# CPU.net
KiCad netlist of a schematic drawn in Altium Designer
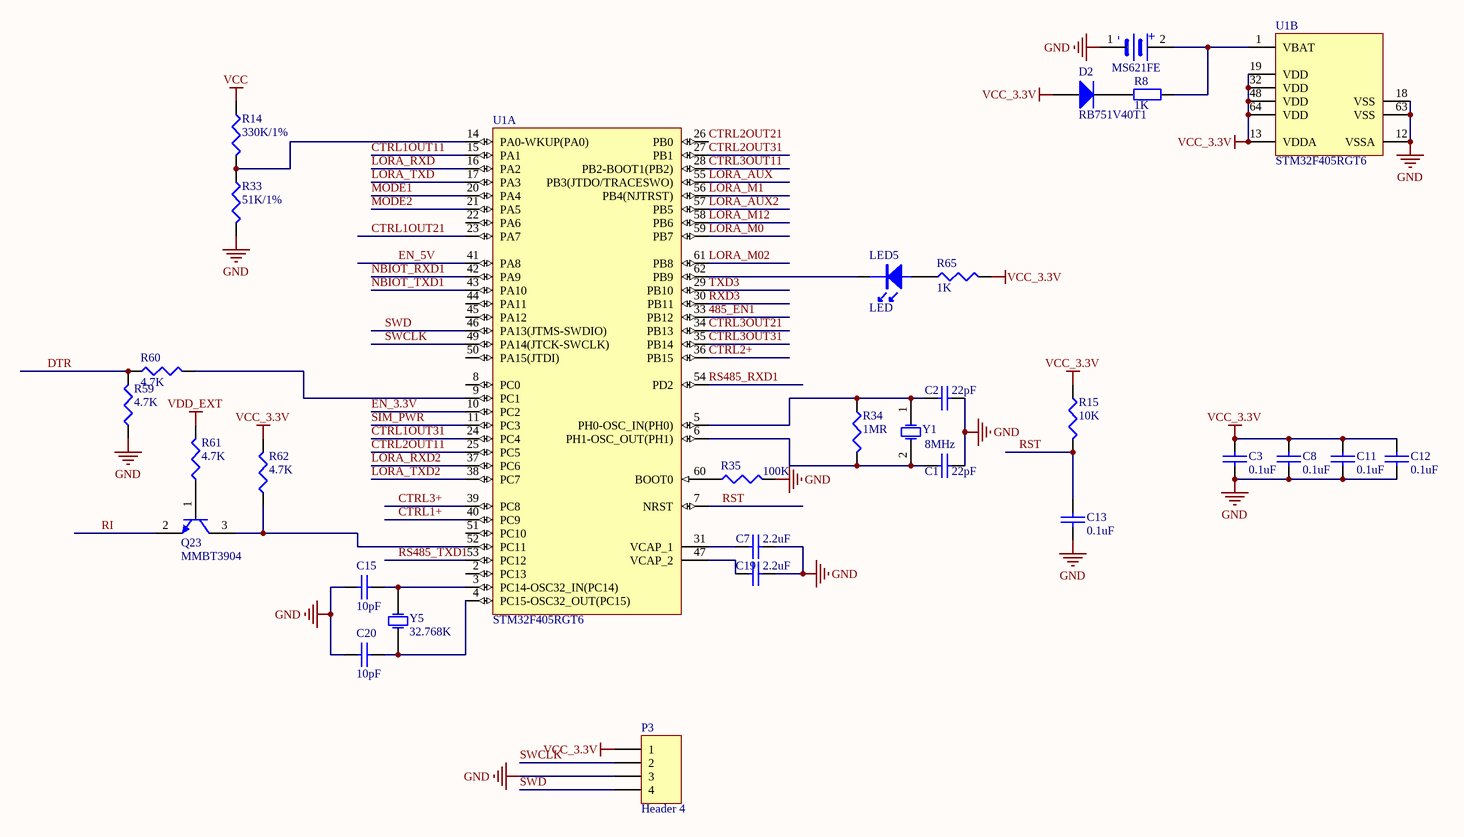
[diagram p0: CPU.SchDoc]

(export (version "E")
  (design (tool "Eeschema 10.0.6"))
  (components
    (comp (ref "C1")
      (value "22pF")
      (footprint "0603c")
      (description "Capacitor")
      (libsource (lib "SM") (part "CAP"))
    )
    (comp (ref "C2")
      (value "22pF")
      (footprint "0603c")
      (description "Capacitor")
      (libsource (lib "SM") (part "CAP"))
    )
    (comp (ref "C3")
      (value "0.1uF")
      (footprint "0603c")
      (description "Capacitor")
      (libsource (lib "SM") (part "CAP"))
    )
    (comp (ref "C7")
      (value "2.2uF")
      (footprint "0603c")
      (description "Capacitor")
      (libsource (lib "SM") (part "CAP"))
    )
    (comp (ref "C8")
      (value "0.1uF")
      (footprint "0603c")
      (description "Capacitor")
      (libsource (lib "SM") (part "CAP"))
    )
    (comp (ref "C11")
      (value "0.1uF")
      (footprint "0603c")
      (description "Capacitor")
      (libsource (lib "SM") (part "CAP"))
    )
    (comp (ref "C12")
      (value "0.1uF")
      (footprint "0603c")
      (description "Capacitor")
      (libsource (lib "SM") (part "CAP"))
    )
    (comp (ref "C13")
      (value "0.1uF")
      (footprint "0603c")
      (description "Capacitor")
      (libsource (lib "SM") (part "CAP"))
    )
    (comp (ref "C15")
      (value "10pF")
      (footprint "0603c")
      (description "Capacitor")
      (libsource (lib "SM") (part "CAP"))
    )
    (comp (ref "C19")
      (value "2.2uF")
      (footprint "0603c")
      (description "Capacitor")
      (libsource (lib "SM") (part "CAP"))
    )
    (comp (ref "C20")
      (value "10pF")
      (footprint "0603c")
      (description "Capacitor")
      (libsource (lib "SM") (part "CAP"))
    )
    (comp (ref "D2")
      (value "RB751V40T1")
      (footprint "SOD323")
      (description "Default Diode")
      (fields (field (name "PUBLISHER") "Altium Limited"))
      (libsource (lib "Miscellaneous Devices") (part "Diode"))
    )
    (comp (ref "LED5") (value "LED") (footprint "0603LED") (libsource (lib "我的元件库") (part "LED")))
    (comp (ref "MS621FE")
      (value "SBatery")
      (footprint "MS621FE")
      (libsource (lib "Myself_1") (part "SBatery"))
    )
    (comp (ref "P3")
      (value "Header 4")
      (footprint "HDR1X4")
      (description "Header, 4-Pin")
      (fields (field (name "PUBLISHER") "Altium Limited"))
      (libsource (lib "Miscellaneous Connectors") (part "Header 4"))
    )
    (comp (ref "Q23") (value "MMBT3904") (footprint "SOT23-3") (libsource (lib "Schlib1") (part "NPN")))
    (comp (ref "R8")
      (value "1K")
      (footprint "0603R")
      (description "Resistor")
      (fields (field (name "PUBLISHER") "Altium Limited"))
      (libsource (lib "Miscellaneous Devices") (part "Res2"))
    )
    (comp (ref "R14")
      (value "330K/1%")
      (footprint "0603R")
      (description "Resistor")
      (fields (field (name "PUBLISHER") "Altium Limited"))
      (libsource (lib "SM") (part "Res3"))
    )
    (comp (ref "R15")
      (value "10K")
      (footprint "0603R")
      (description "Resistor")
      (fields (field (name "PUBLISHER") "Altium Limited"))
      (libsource (lib "SM") (part "Res3"))
    )
    (comp (ref "R33")
      (value "51K/1%")
      (footprint "0603R")
      (description "Resistor")
      (fields (field (name "PUBLISHER") "Altium Limited"))
      (libsource (lib "SM") (part "Res3"))
    )
    (comp (ref "R34")
      (value "1MR")
      (footprint "0603R")
      (description "Resistor")
      (fields (field (name "PUBLISHER") "Altium Limited"))
      (libsource (lib "SM") (part "Res3"))
    )
    (comp (ref "R35")
      (value "100K")
      (footprint "0603R")
      (description "Resistor")
      (fields (field (name "PUBLISHER") "Altium Limited"))
      (libsource (lib "SM") (part "Res3"))
    )
    (comp (ref "R59")
      (value "4.7K")
      (footprint "0603R")
      (libsource (lib "ZWLIntegrated_Library") (part "RES1"))
    )
    (comp (ref "R60")
      (value "4.7K")
      (footprint "0603R")
      (libsource (lib "ZWLIntegrated_Library") (part "RES1"))
    )
    (comp (ref "R61")
      (value "4.7K")
      (footprint "0603R")
      (libsource (lib "ZWLIntegrated_Library") (part "RES1"))
    )
    (comp (ref "R62")
      (value "4.7K")
      (footprint "0603R")
      (libsource (lib "ZWLIntegrated_Library") (part "RES1"))
    )
    (comp (ref "R65")
      (value "1K")
      (footprint "0603R")
      (libsource (lib "ZWLIntegrated_Library") (part "RES1"))
    )
    (comp (ref "U1")
      (value "STM32F405RGT6")
      (footprint "LQFP-64")
      (fields (field (name "MANUFACTURER") "STMicroelectronics"))
      (libsource (lib "STMicroelectronics STM32 F4") (part "STM32F405RGT6"))
    )
    (comp (ref "Y1")
      (value "8MHz")
      (footprint "CRAY_5032")
      (description "Crystal Oscillator")
      (fields (field (name "PUBLISHER") "Altium Limited"))
      (libsource (lib "Miscellaneous Devices") (part "XTAL"))
    )
    (comp (ref "Y5")
      (value "32.768K")
      (footprint "32.768K")
      (description "Crystal Oscillator")
      (fields (field (name "PUBLISHER") "Altium Limited"))
      (libsource (lib "") (part "XTAL_1"))
    )
  )
  (nets
    (net (code "1") (name "/485_EN1") (class "Default")
      (node (ref "U1") (pin "33") (pinfunction "PB12_33") (pintype "bidirectional"))
    )
    (net (code "2") (name "/CTRL1+") (class "Default")
      (node (ref "U1") (pin "40") (pinfunction "PC9_40") (pintype "bidirectional"))
    )
    (net (code "3") (name "/CTRL1OUT11") (class "Default")
      (node (ref "U1") (pin "15") (pinfunction "PA1_15") (pintype "bidirectional"))
    )
    (net (code "4") (name "/CTRL1OUT21") (class "Default")
      (node (ref "U1") (pin "23") (pinfunction "PA7_23") (pintype "bidirectional"))
    )
    (net (code "5") (name "/CTRL1OUT31") (class "Default")
      (node (ref "U1") (pin "24") (pinfunction "PC4_24") (pintype "bidirectional"))
    )
    (net (code "6") (name "/CTRL2+") (class "Default")
      (node (ref "U1") (pin "36") (pinfunction "PB15_36") (pintype "bidirectional"))
    )
    (net (code "7") (name "/CTRL2OUT11") (class "Default")
      (node (ref "U1") (pin "25") (pinfunction "PC5_25") (pintype "bidirectional"))
    )
    (net (code "8") (name "/CTRL2OUT21") (class "Default")
      (node (ref "U1") (pin "26") (pinfunction "PB0_26") (pintype "bidirectional"))
    )
    (net (code "9") (name "/CTRL2OUT31") (class "Default")
      (node (ref "U1") (pin "27") (pinfunction "PB1_27") (pintype "bidirectional"))
    )
    (net (code "10") (name "/CTRL3+") (class "Default")
      (node (ref "U1") (pin "39") (pinfunction "PC8_39") (pintype "bidirectional"))
    )
    (net (code "11") (name "/CTRL3OUT11") (class "Default")
      (node (ref "U1") (pin "28") (pinfunction "PB2-BOOT1(PB2)_28") (pintype "bidirectional"))
    )
    (net (code "12") (name "/CTRL3OUT21") (class "Default")
      (node (ref "U1") (pin "34") (pinfunction "PB13_34") (pintype "bidirectional"))
    )
    (net (code "13") (name "/CTRL3OUT31") (class "Default")
      (node (ref "U1") (pin "35") (pinfunction "PB14_35") (pintype "bidirectional"))
    )
    (net (code "14") (name "/DTR") (class "Default")
      (node (ref "R59") (pin "2") (pinfunction "2_2") (pintype "passive"))
      (node (ref "R60") (pin "1") (pinfunction "1_1") (pintype "passive"))
    )
    (net (code "15") (name "/EN_3.3V") (class "Default")
      (node (ref "U1") (pin "10") (pinfunction "PC2_10") (pintype "bidirectional"))
    )
    (net (code "16") (name "/EN_5V") (class "Default")
      (node (ref "U1") (pin "41") (pinfunction "PA8_41") (pintype "bidirectional"))
    )
    (net (code "17") (name "/LORA_AUX") (class "Default")
      (node (ref "U1") (pin "55") (pinfunction "PB3(JTDO/TRACESWO)_55") (pintype "bidirectional"))
    )
    (net (code "18") (name "/LORA_AUX2") (class "Default")
      (node (ref "U1") (pin "57") (pinfunction "PB5_57") (pintype "bidirectional"))
    )
    (net (code "19") (name "/LORA_M0") (class "Default")
      (node (ref "U1") (pin "59") (pinfunction "PB7_59") (pintype "bidirectional"))
    )
    (net (code "20") (name "/LORA_M1") (class "Default")
      (node (ref "U1") (pin "56") (pinfunction "PB4(NJTRST)_56") (pintype "bidirectional"))
    )
    (net (code "21") (name "/LORA_M02") (class "Default")
      (node (ref "U1") (pin "61") (pinfunction "PB8_61") (pintype "bidirectional"))
    )
    (net (code "22") (name "/LORA_M12") (class "Default")
      (node (ref "U1") (pin "58") (pinfunction "PB6_58") (pintype "bidirectional"))
    )
    (net (code "23") (name "/LORA_RXD") (class "Default")
      (node (ref "U1") (pin "16") (pinfunction "PA2_16") (pintype "bidirectional"))
    )
    (net (code "24") (name "/LORA_RXD2") (class "Default")
      (node (ref "U1") (pin "37") (pinfunction "PC6_37") (pintype "bidirectional"))
    )
    (net (code "25") (name "/LORA_TXD") (class "Default")
      (node (ref "U1") (pin "17") (pinfunction "PA3_17") (pintype "bidirectional"))
    )
    (net (code "26") (name "/LORA_TXD2") (class "Default")
      (node (ref "U1") (pin "38") (pinfunction "PC7_38") (pintype "bidirectional"))
    )
    (net (code "27") (name "/MODE1") (class "Default")
      (node (ref "U1") (pin "20") (pinfunction "PA4_20") (pintype "bidirectional"))
    )
    (net (code "28") (name "/MODE2") (class "Default")
      (node (ref "U1") (pin "21") (pinfunction "PA5_21") (pintype "bidirectional"))
    )
    (net (code "29") (name "/NBIOT_RXD1") (class "Default")
      (node (ref "U1") (pin "42") (pinfunction "PA9_42") (pintype "bidirectional"))
    )
    (net (code "30") (name "/NBIOT_TXD1") (class "Default")
      (node (ref "U1") (pin "43") (pinfunction "PA10_43") (pintype "bidirectional"))
    )
    (net (code "31") (name "/RI") (class "Default")
      (node (ref "Q23") (pin "2") (pinfunction "E_2") (pintype "passive"))
    )
    (net (code "32") (name "/RS485_RXD1") (class "Default")
      (node (ref "U1") (pin "54") (pinfunction "PD2_54") (pintype "bidirectional"))
    )
    (net (code "33") (name "/RS485_TXD1") (class "Default")
      (node (ref "U1") (pin "53") (pinfunction "PC12_53") (pintype "bidirectional"))
    )
    (net (code "34") (name "/RST") (class "Default")
      (node (ref "C13") (pin "2") (pinfunction "2_2") (pintype "passive"))
      (node (ref "R15") (pin "2") (pinfunction "2_2") (pintype "passive"))
      (node (ref "U1") (pin "7") (pinfunction "NRST_7") (pintype "bidirectional"))
    )
    (net (code "35") (name "/RXD3") (class "Default")
      (node (ref "U1") (pin "30") (pinfunction "PB11_30") (pintype "bidirectional"))
    )
    (net (code "36") (name "/SIM_PWR") (class "Default")
      (node (ref "U1") (pin "11") (pinfunction "PC3_11") (pintype "bidirectional"))
    )
    (net (code "37") (name "/SWCLK") (class "Default")
      (node (ref "P3") (pin "2") (pinfunction "2_2") (pintype "passive"))
      (node (ref "U1") (pin "49") (pinfunction "PA14(JTCK-SWCLK)_49") (pintype "bidirectional"))
    )
    (net (code "38") (name "/SWD") (class "Default")
      (node (ref "P3") (pin "4") (pinfunction "4_4") (pintype "passive"))
      (node (ref "U1") (pin "46") (pinfunction "PA13(JTMS-SWDIO)_46") (pintype "bidirectional"))
    )
    (net (code "39") (name "/TXD3") (class "Default")
      (node (ref "U1") (pin "29") (pinfunction "PB10_29") (pintype "bidirectional"))
    )
    (net (code "40") (name "GND") (class "Default")
      (node (ref "C1") (pin "1") (pinfunction "1_1") (pintype "passive"))
      (node (ref "C11") (pin "1") (pinfunction "1_1") (pintype "passive"))
      (node (ref "C12") (pin "1") (pinfunction "1_1") (pintype "passive"))
      (node (ref "C13") (pin "1") (pinfunction "1_1") (pintype "passive"))
      (node (ref "C15") (pin "1") (pinfunction "1_1") (pintype "passive"))
      (node (ref "C19") (pin "1") (pinfunction "1_1") (pintype "passive"))
      (node (ref "C2") (pin "1") (pinfunction "1_1") (pintype "passive"))
      (node (ref "C20") (pin "1") (pinfunction "1_1") (pintype "passive"))
      (node (ref "C3") (pin "1") (pinfunction "1_1") (pintype "passive"))
      (node (ref "C7") (pin "1") (pinfunction "1_1") (pintype "passive"))
      (node (ref "C8") (pin "1") (pinfunction "1_1") (pintype "passive"))
      (node (ref "MS621FE") (pin "1") (pinfunction "1_1") (pintype "passive"))
      (node (ref "P3") (pin "3") (pinfunction "3_3") (pintype "passive"))
      (node (ref "R33") (pin "2") (pinfunction "2_2") (pintype "passive"))
      (node (ref "R35") (pin "2") (pinfunction "2_2") (pintype "passive"))
      (node (ref "R59") (pin "1") (pinfunction "1_1") (pintype "passive"))
      (node (ref "U1") (pin "12") (pinfunction "VSSA_12") (pintype "power_in"))
      (node (ref "U1") (pin "18") (pinfunction "VSS_18") (pintype "power_in"))
      (node (ref "U1") (pin "63") (pinfunction "VSS_63") (pintype "power_in"))
    )
    (net (code "41") (name "Net-(D2-K)") (class "Default")
      (node (ref "D2") (pin "2") (pinfunction "K_2") (pintype "passive"))
      (node (ref "R8") (pin "1") (pinfunction "1_1") (pintype "passive"))
    )
    (net (code "42") (name "Net-(LED5-Pad1)") (class "Default")
      (node (ref "LED5") (pin "1") (pinfunction "1_1") (pintype "passive"))
      (node (ref "R65") (pin "1") (pinfunction "1_1") (pintype "passive"))
    )
    (net (code "43") (name "Net-(Q23-B)") (class "Default")
      (node (ref "Q23") (pin "1") (pinfunction "B_1") (pintype "passive"))
      (node (ref "R61") (pin "1") (pinfunction "1_1") (pintype "passive"))
    )
    (net (code "44") (name "Net-(Q23-C)") (class "Default")
      (node (ref "Q23") (pin "3") (pinfunction "C_3") (pintype "passive"))
      (node (ref "R62") (pin "1") (pinfunction "1_1") (pintype "passive"))
      (node (ref "U1") (pin "52") (pinfunction "PC11_52") (pintype "bidirectional"))
    )
    (net (code "45") (name "Net-(U1A-BOOT0)") (class "Default")
      (node (ref "R35") (pin "1") (pinfunction "1_1") (pintype "passive"))
      (node (ref "U1") (pin "60") (pinfunction "BOOT0_60") (pintype "input"))
    )
    (net (code "46") (name "Net-(U1A-PA0-WKUP(PA0))") (class "Default")
      (node (ref "R14") (pin "2") (pinfunction "2_2") (pintype "passive"))
      (node (ref "R33") (pin "1") (pinfunction "1_1") (pintype "passive"))
      (node (ref "U1") (pin "14") (pinfunction "PA0-WKUP(PA0)_14") (pintype "bidirectional"))
    )
    (net (code "47") (name "Net-(U1A-PB9)") (class "Default")
      (node (ref "LED5") (pin "2") (pinfunction "2_2") (pintype "passive"))
      (node (ref "U1") (pin "62") (pinfunction "PB9_62") (pintype "bidirectional"))
    )
    (net (code "48") (name "Net-(U1A-PC1)") (class "Default")
      (node (ref "R60") (pin "2") (pinfunction "2_2") (pintype "passive"))
      (node (ref "U1") (pin "9") (pinfunction "PC1_9") (pintype "bidirectional"))
    )
    (net (code "49") (name "Net-(U1A-PC14-OSC32_IN(PC14))") (class "Default")
      (node (ref "C15") (pin "2") (pinfunction "2_2") (pintype "passive"))
      (node (ref "U1") (pin "3") (pinfunction "PC14-OSC32_IN(PC14)_3") (pintype "bidirectional"))
      (node (ref "Y5") (pin "1") (pinfunction "OSC1_1") (pintype "passive"))
    )
    (net (code "50") (name "Net-(U1A-PC15-OSC32_OUT(PC15))") (class "Default")
      (node (ref "C20") (pin "2") (pinfunction "2_2") (pintype "passive"))
      (node (ref "U1") (pin "4") (pinfunction "PC15-OSC32_OUT(PC15)_4") (pintype "bidirectional"))
      (node (ref "Y5") (pin "2") (pinfunction "OSC2_2") (pintype "passive"))
    )
    (net (code "51") (name "Net-(U1A-PH0-OSC_IN(PH0))") (class "Default")
      (node (ref "C2") (pin "2") (pinfunction "2_2") (pintype "passive"))
      (node (ref "R34") (pin "1") (pinfunction "1_1") (pintype "passive"))
      (node (ref "U1") (pin "5") (pinfunction "PH0-OSC_IN(PH0)_5") (pintype "bidirectional"))
      (node (ref "Y1") (pin "1") (pinfunction "OSC1_1") (pintype "passive"))
    )
    (net (code "52") (name "Net-(U1A-PH1-OSC_OUT(PH1))") (class "Default")
      (node (ref "C1") (pin "2") (pinfunction "2_2") (pintype "passive"))
      (node (ref "R34") (pin "2") (pinfunction "2_2") (pintype "passive"))
      (node (ref "U1") (pin "6") (pinfunction "PH1-OSC_OUT(PH1)_6") (pintype "bidirectional"))
      (node (ref "Y1") (pin "2") (pinfunction "OSC2_2") (pintype "passive"))
    )
    (net (code "53") (name "Net-(U1A-VCAP_1)") (class "Default")
      (node (ref "C7") (pin "2") (pinfunction "2_2") (pintype "passive"))
      (node (ref "U1") (pin "31") (pinfunction "VCAP_1_31") (pintype "power_in"))
    )
    (net (code "54") (name "Net-(U1A-VCAP_2)") (class "Default")
      (node (ref "C19") (pin "2") (pinfunction "2_2") (pintype "passive"))
      (node (ref "U1") (pin "47") (pinfunction "VCAP_2_47") (pintype "power_in"))
    )
    (net (code "55") (name "Net-(U1B-VBAT)") (class "Default")
      (node (ref "MS621FE") (pin "2") (pinfunction "2_2") (pintype "passive"))
      (node (ref "R8") (pin "2") (pinfunction "2_2") (pintype "passive"))
      (node (ref "U1") (pin "1") (pinfunction "VBAT_1") (pintype "power_in"))
    )
    (net (code "56") (name "VCC") (class "Default")
      (node (ref "R14") (pin "1") (pinfunction "1_1") (pintype "passive"))
    )
    (net (code "57") (name "VCC_3.3V") (class "Default")
      (node (ref "C11") (pin "2") (pinfunction "2_2") (pintype "passive"))
      (node (ref "C12") (pin "2") (pinfunction "2_2") (pintype "passive"))
      (node (ref "C3") (pin "2") (pinfunction "2_2") (pintype "passive"))
      (node (ref "C8") (pin "2") (pinfunction "2_2") (pintype "passive"))
      (node (ref "D2") (pin "1") (pinfunction "A_1") (pintype "passive"))
      (node (ref "P3") (pin "1") (pinfunction "1_1") (pintype "passive"))
      (node (ref "R15") (pin "1") (pinfunction "1_1") (pintype "passive"))
      (node (ref "R62") (pin "2") (pinfunction "2_2") (pintype "passive"))
      (node (ref "R65") (pin "2") (pinfunction "2_2") (pintype "passive"))
      (node (ref "U1") (pin "13") (pinfunction "VDDA_13") (pintype "power_in"))
      (node (ref "U1") (pin "19") (pinfunction "VDD_19") (pintype "power_in"))
      (node (ref "U1") (pin "32") (pinfunction "VDD_32") (pintype "power_in"))
      (node (ref "U1") (pin "48") (pinfunction "VDD_48") (pintype "power_in"))
      (node (ref "U1") (pin "64") (pinfunction "VDD_64") (pintype "power_in"))
    )
    (net (code "58") (name "VDD_EXT") (class "Default")
      (node (ref "R61") (pin "2") (pinfunction "2_2") (pintype "passive"))
    )
    (net (code "59") (name "unconnected-(U1A-PA6-Pad22)") (class "Default")
      (node (ref "U1") (pin "22") (pinfunction "PA6_22") (pintype "bidirectional"))
    )
    (net (code "60") (name "unconnected-(U1A-PA11-Pad44)") (class "Default")
      (node (ref "U1") (pin "44") (pinfunction "PA11_44") (pintype "bidirectional"))
    )
    (net (code "61") (name "unconnected-(U1A-PA12-Pad45)") (class "Default")
      (node (ref "U1") (pin "45") (pinfunction "PA12_45") (pintype "bidirectional"))
    )
    (net (code "62") (name "unconnected-(U1A-PA15(JTDI)-Pad50)") (class "Default")
      (node (ref "U1") (pin "50") (pinfunction "PA15(JTDI)_50") (pintype "bidirectional"))
    )
    (net (code "63") (name "unconnected-(U1A-PC0-Pad8)") (class "Default")
      (node (ref "U1") (pin "8") (pinfunction "PC0_8") (pintype "bidirectional"))
    )
    (net (code "64") (name "unconnected-(U1A-PC10-Pad51)") (class "Default")
      (node (ref "U1") (pin "51") (pinfunction "PC10_51") (pintype "bidirectional"))
    )
    (net (code "65") (name "unconnected-(U1A-PC13-Pad2)") (class "Default")
      (node (ref "U1") (pin "2") (pinfunction "PC13_2") (pintype "bidirectional"))
    )
  )
)
